# Mosfet_SSR.net
KiCad netlist of a schematic drawn in Altium Designer
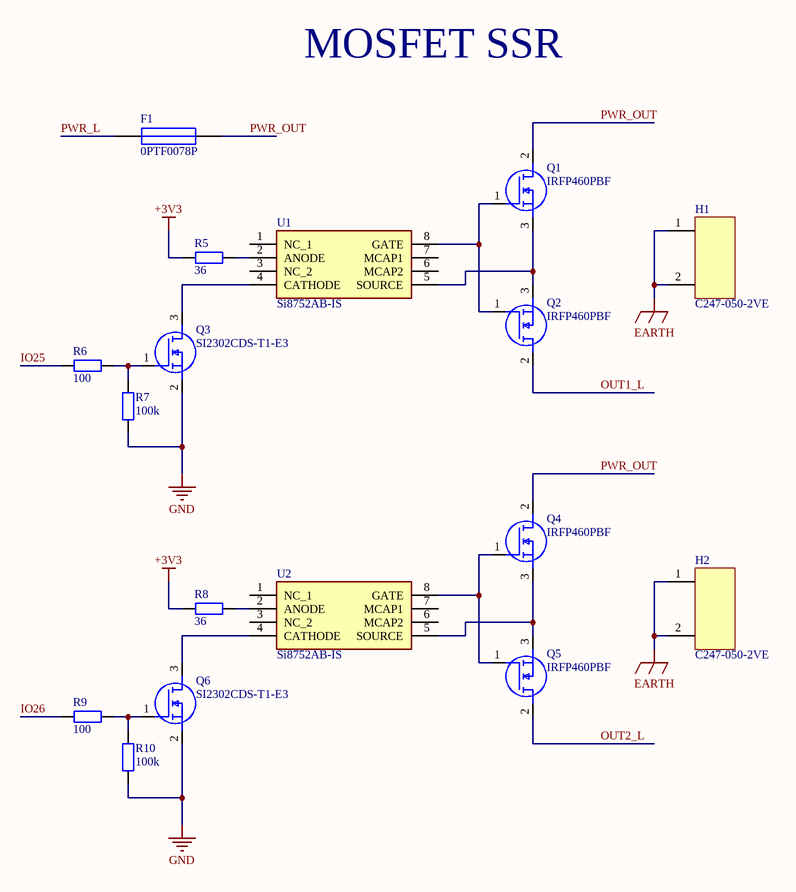
[diagram p0: Mosfet_SSR.SchDoc]

(export (version "E")
  (design (tool "Eeschema 10.0.6"))
  (components
    (comp (ref "F1")
      (value "0PTF0078P")
      (footprint "FH1-200CK-B")
      (description "Fuse holder")
      (fields (field (name "MOUSER PART NUMBER") "576-0PTF0078P"))
      (libsource (lib "SamacSys") (part "0PTF0078P"))
    )
    (comp (ref "H1")
      (value "C247-050-2VE")
      (footprint "C247-050-2VE")
      (description "Heatsink")
      (libsource (lib "SamacSys") (part "C247-050-2VE"))
    )
    (comp (ref "H2")
      (value "C247-050-2VE")
      (footprint "C247-050-2VE")
      (description "Heatsink")
      (libsource (lib "SamacSys") (part "C247-050-2VE"))
    )
    (comp (ref "Q1")
      (value "IRFP460PBF")
      (footprint "SamacSys:TO546P531X1558X2511-3P")
      (description "MOSFET (N-Channel)")
      (fields (field (name "MOUSER PART NUMBER") "844-IRFP460PBF"))
      (libsource (lib "*") (part "IRFP460PBF"))
    )
    (comp (ref "Q2")
      (value "IRFP460PBF")
      (footprint "SamacSys:TO546P531X1558X2511-3P")
      (description "MOSFET (N-Channel)")
      (fields (field (name "MOUSER PART NUMBER") "844-IRFP460PBF"))
      (libsource (lib "*") (part "IRFP460PBF"))
    )
    (comp (ref "Q3")
      (value "SI2302CDS-T1-E3")
      (footprint "SamacSys:SOT95P237X112-3N")
      (description "MOSFET (N-Channel)")
      (fields (field (name "MOUSER PART NUMBER") "781-SI2302CDS-E3"))
      (libsource (lib "SamacSys") (part "SI2302CDS-T1-E3"))
    )
    (comp (ref "Q4")
      (value "IRFP460PBF")
      (footprint "SamacSys:TO546P531X1558X2511-3P")
      (description "MOSFET (N-Channel)")
      (fields (field (name "MOUSER PART NUMBER") "844-IRFP460PBF"))
      (libsource (lib "*") (part "IRFP460PBF"))
    )
    (comp (ref "Q5")
      (value "IRFP460PBF")
      (footprint "SamacSys:TO546P531X1558X2511-3P")
      (description "MOSFET (N-Channel)")
      (fields (field (name "MOUSER PART NUMBER") "844-IRFP460PBF"))
      (libsource (lib "*") (part "IRFP460PBF"))
    )
    (comp (ref "Q6")
      (value "SI2302CDS-T1-E3")
      (footprint "SamacSys:SOT95P237X112-3N")
      (description "MOSFET (N-Channel)")
      (fields (field (name "MOUSER PART NUMBER") "781-SI2302CDS-E3"))
      (libsource (lib "SamacSys") (part "SI2302CDS-T1-E3"))
    )
    (comp (ref "R5")
      (value "36")
      (footprint "R2012_0805I_N")
      (description "R")
      (libsource (lib "General") (part "R"))
    )
    (comp (ref "R6")
      (value "100")
      (footprint "R2012_0805I_N")
      (description "R")
      (libsource (lib "General") (part "R"))
    )
    (comp (ref "R7")
      (value "100k")
      (footprint "R2012_0805I_N")
      (description "R")
      (libsource (lib "General") (part "R"))
    )
    (comp (ref "R8")
      (value "36")
      (footprint "R2012_0805I_N")
      (description "R")
      (libsource (lib "General") (part "R"))
    )
    (comp (ref "R9")
      (value "100")
      (footprint "R2012_0805I_N")
      (description "R")
      (libsource (lib "General") (part "R"))
    )
    (comp (ref "R10")
      (value "100k")
      (footprint "R2012_0805I_N")
      (description "R")
      (libsource (lib "General") (part "R"))
    )
    (comp (ref "U1")
      (value "Si8752AB-IS")
      (footprint "SamacSys:SOIC127P600X175-8N")
      (description "Integrated Circuit")
      (fields
        (field (name "MOUSER PART NUMBER") "634-SI8752AB-IS")
        (field (name "ARROW PART NUMBER") "SI8752AB-IS")
      )
      (libsource (lib "SamacSys") (part "Si8752AB-IS"))
    )
    (comp (ref "U2")
      (value "Si8752AB-IS")
      (footprint "SamacSys:SOIC127P600X175-8N")
      (description "Integrated Circuit")
      (fields
        (field (name "MOUSER PART NUMBER") "634-SI8752AB-IS")
        (field (name "ARROW PART NUMBER") "SI8752AB-IS")
      )
      (libsource (lib "SamacSys") (part "Si8752AB-IS"))
    )
  )
  (nets
    (net (code "1") (name "+3V3") (class "Default")
      (node (ref "R5") (pin "2") (pintype "passive"))
      (node (ref "R8") (pin "2") (pintype "passive"))
    )
    (net (code "2") (name "/IO25") (class "Default") (node (ref "R6") (pin "2") (pintype "passive")))
    (net (code "3") (name "/IO26") (class "Default") (node (ref "R9") (pin "2") (pintype "passive")))
    (net (code "4") (name "/OUT1_L") (class "Default")
      (node (ref "Q2") (pin "2") (pinfunction "D_2") (pintype "passive"))
    )
    (net (code "5") (name "/OUT2_L") (class "Default")
      (node (ref "Q5") (pin "2") (pinfunction "D_2") (pintype "passive"))
    )
    (net (code "6") (name "/PWR_L") (class "Default") (node (ref "F1") (pin "1") (pintype "passive")))
    (net (code "7") (name "/PWR_OUT") (class "Default")
      (node (ref "F1") (pin "2") (pintype "passive"))
      (node (ref "Q1") (pin "2") (pinfunction "D_2") (pintype "passive"))
      (node (ref "Q4") (pin "2") (pinfunction "D_2") (pintype "passive"))
    )
    (net (code "8") (name "EARTH") (class "Default")
      (node (ref "H1") (pin "1") (pintype "passive"))
      (node (ref "H1") (pin "2") (pintype "passive"))
      (node (ref "H2") (pin "1") (pintype "passive"))
      (node (ref "H2") (pin "2") (pintype "passive"))
    )
    (net (code "9") (name "GND") (class "Default")
      (node (ref "Q3") (pin "2") (pinfunction "S_2") (pintype "passive"))
      (node (ref "Q6") (pin "2") (pinfunction "S_2") (pintype "passive"))
      (node (ref "R10") (pin "1") (pintype "passive"))
      (node (ref "R7") (pin "1") (pintype "passive"))
    )
    (net (code "10") (name "Net-(Q1-G)") (class "Default")
      (node (ref "Q1") (pin "1") (pinfunction "G_1") (pintype "passive"))
      (node (ref "Q2") (pin "1") (pinfunction "G_1") (pintype "passive"))
      (node (ref "U1") (pin "8") (pinfunction "GATE_8") (pintype "passive"))
    )
    (net (code "11") (name "Net-(Q1-S)") (class "Default")
      (node (ref "Q1") (pin "3") (pinfunction "S_3") (pintype "passive"))
      (node (ref "Q2") (pin "3") (pinfunction "S_3") (pintype "passive"))
      (node (ref "U1") (pin "5") (pinfunction "SOURCE_5") (pintype "passive"))
    )
    (net (code "12") (name "Net-(Q3-D)") (class "Default")
      (node (ref "Q3") (pin "3") (pinfunction "D_3") (pintype "passive"))
      (node (ref "U1") (pin "4") (pinfunction "CATHODE_4") (pintype "passive"))
    )
    (net (code "13") (name "Net-(Q3-G)") (class "Default")
      (node (ref "Q3") (pin "1") (pinfunction "G_1") (pintype "passive"))
      (node (ref "R6") (pin "1") (pintype "passive"))
      (node (ref "R7") (pin "2") (pintype "passive"))
    )
    (net (code "14") (name "Net-(Q4-G)") (class "Default")
      (node (ref "Q4") (pin "1") (pinfunction "G_1") (pintype "passive"))
      (node (ref "Q5") (pin "1") (pinfunction "G_1") (pintype "passive"))
      (node (ref "U2") (pin "8") (pinfunction "GATE_8") (pintype "passive"))
    )
    (net (code "15") (name "Net-(Q4-S)") (class "Default")
      (node (ref "Q4") (pin "3") (pinfunction "S_3") (pintype "passive"))
      (node (ref "Q5") (pin "3") (pinfunction "S_3") (pintype "passive"))
      (node (ref "U2") (pin "5") (pinfunction "SOURCE_5") (pintype "passive"))
    )
    (net (code "16") (name "Net-(Q6-D)") (class "Default")
      (node (ref "Q6") (pin "3") (pinfunction "D_3") (pintype "passive"))
      (node (ref "U2") (pin "4") (pinfunction "CATHODE_4") (pintype "passive"))
    )
    (net (code "17") (name "Net-(Q6-G)") (class "Default")
      (node (ref "Q6") (pin "1") (pinfunction "G_1") (pintype "passive"))
      (node (ref "R10") (pin "2") (pintype "passive"))
      (node (ref "R9") (pin "1") (pintype "passive"))
    )
    (net (code "18") (name "Net-(U1-ANODE)") (class "Default")
      (node (ref "R5") (pin "1") (pintype "passive"))
      (node (ref "U1") (pin "2") (pinfunction "ANODE_2") (pintype "passive"))
    )
    (net (code "19") (name "Net-(U2-ANODE)") (class "Default")
      (node (ref "R8") (pin "1") (pintype "passive"))
      (node (ref "U2") (pin "2") (pinfunction "ANODE_2") (pintype "passive"))
    )
    (net (code "20") (name "unconnected-(U1-MCAP1-Pad7)") (class "Default")
      (node (ref "U1") (pin "7") (pinfunction "MCAP1_7") (pintype "passive"))
    )
    (net (code "21") (name "unconnected-(U1-MCAP2-Pad6)") (class "Default")
      (node (ref "U1") (pin "6") (pinfunction "MCAP2_6") (pintype "passive"))
    )
    (net (code "22") (name "unconnected-(U1-NC_1-Pad1)") (class "Default")
      (node (ref "U1") (pin "1") (pinfunction "NC_1_1") (pintype "passive"))
    )
    (net (code "23") (name "unconnected-(U1-NC_2-Pad3)") (class "Default")
      (node (ref "U1") (pin "3") (pinfunction "NC_2_3") (pintype "passive"))
    )
    (net (code "24") (name "unconnected-(U2-MCAP1-Pad7)") (class "Default")
      (node (ref "U2") (pin "7") (pinfunction "MCAP1_7") (pintype "passive"))
    )
    (net (code "25") (name "unconnected-(U2-MCAP2-Pad6)") (class "Default")
      (node (ref "U2") (pin "6") (pinfunction "MCAP2_6") (pintype "passive"))
    )
    (net (code "26") (name "unconnected-(U2-NC_1-Pad1)") (class "Default")
      (node (ref "U2") (pin "1") (pinfunction "NC_1_1") (pintype "passive"))
    )
    (net (code "27") (name "unconnected-(U2-NC_2-Pad3)") (class "Default")
      (node (ref "U2") (pin "3") (pinfunction "NC_2_3") (pintype "passive"))
    )
  )
)
